# CH32F205RBT6-R1.net
KiCad netlist of a schematic drawn in Altium Designer
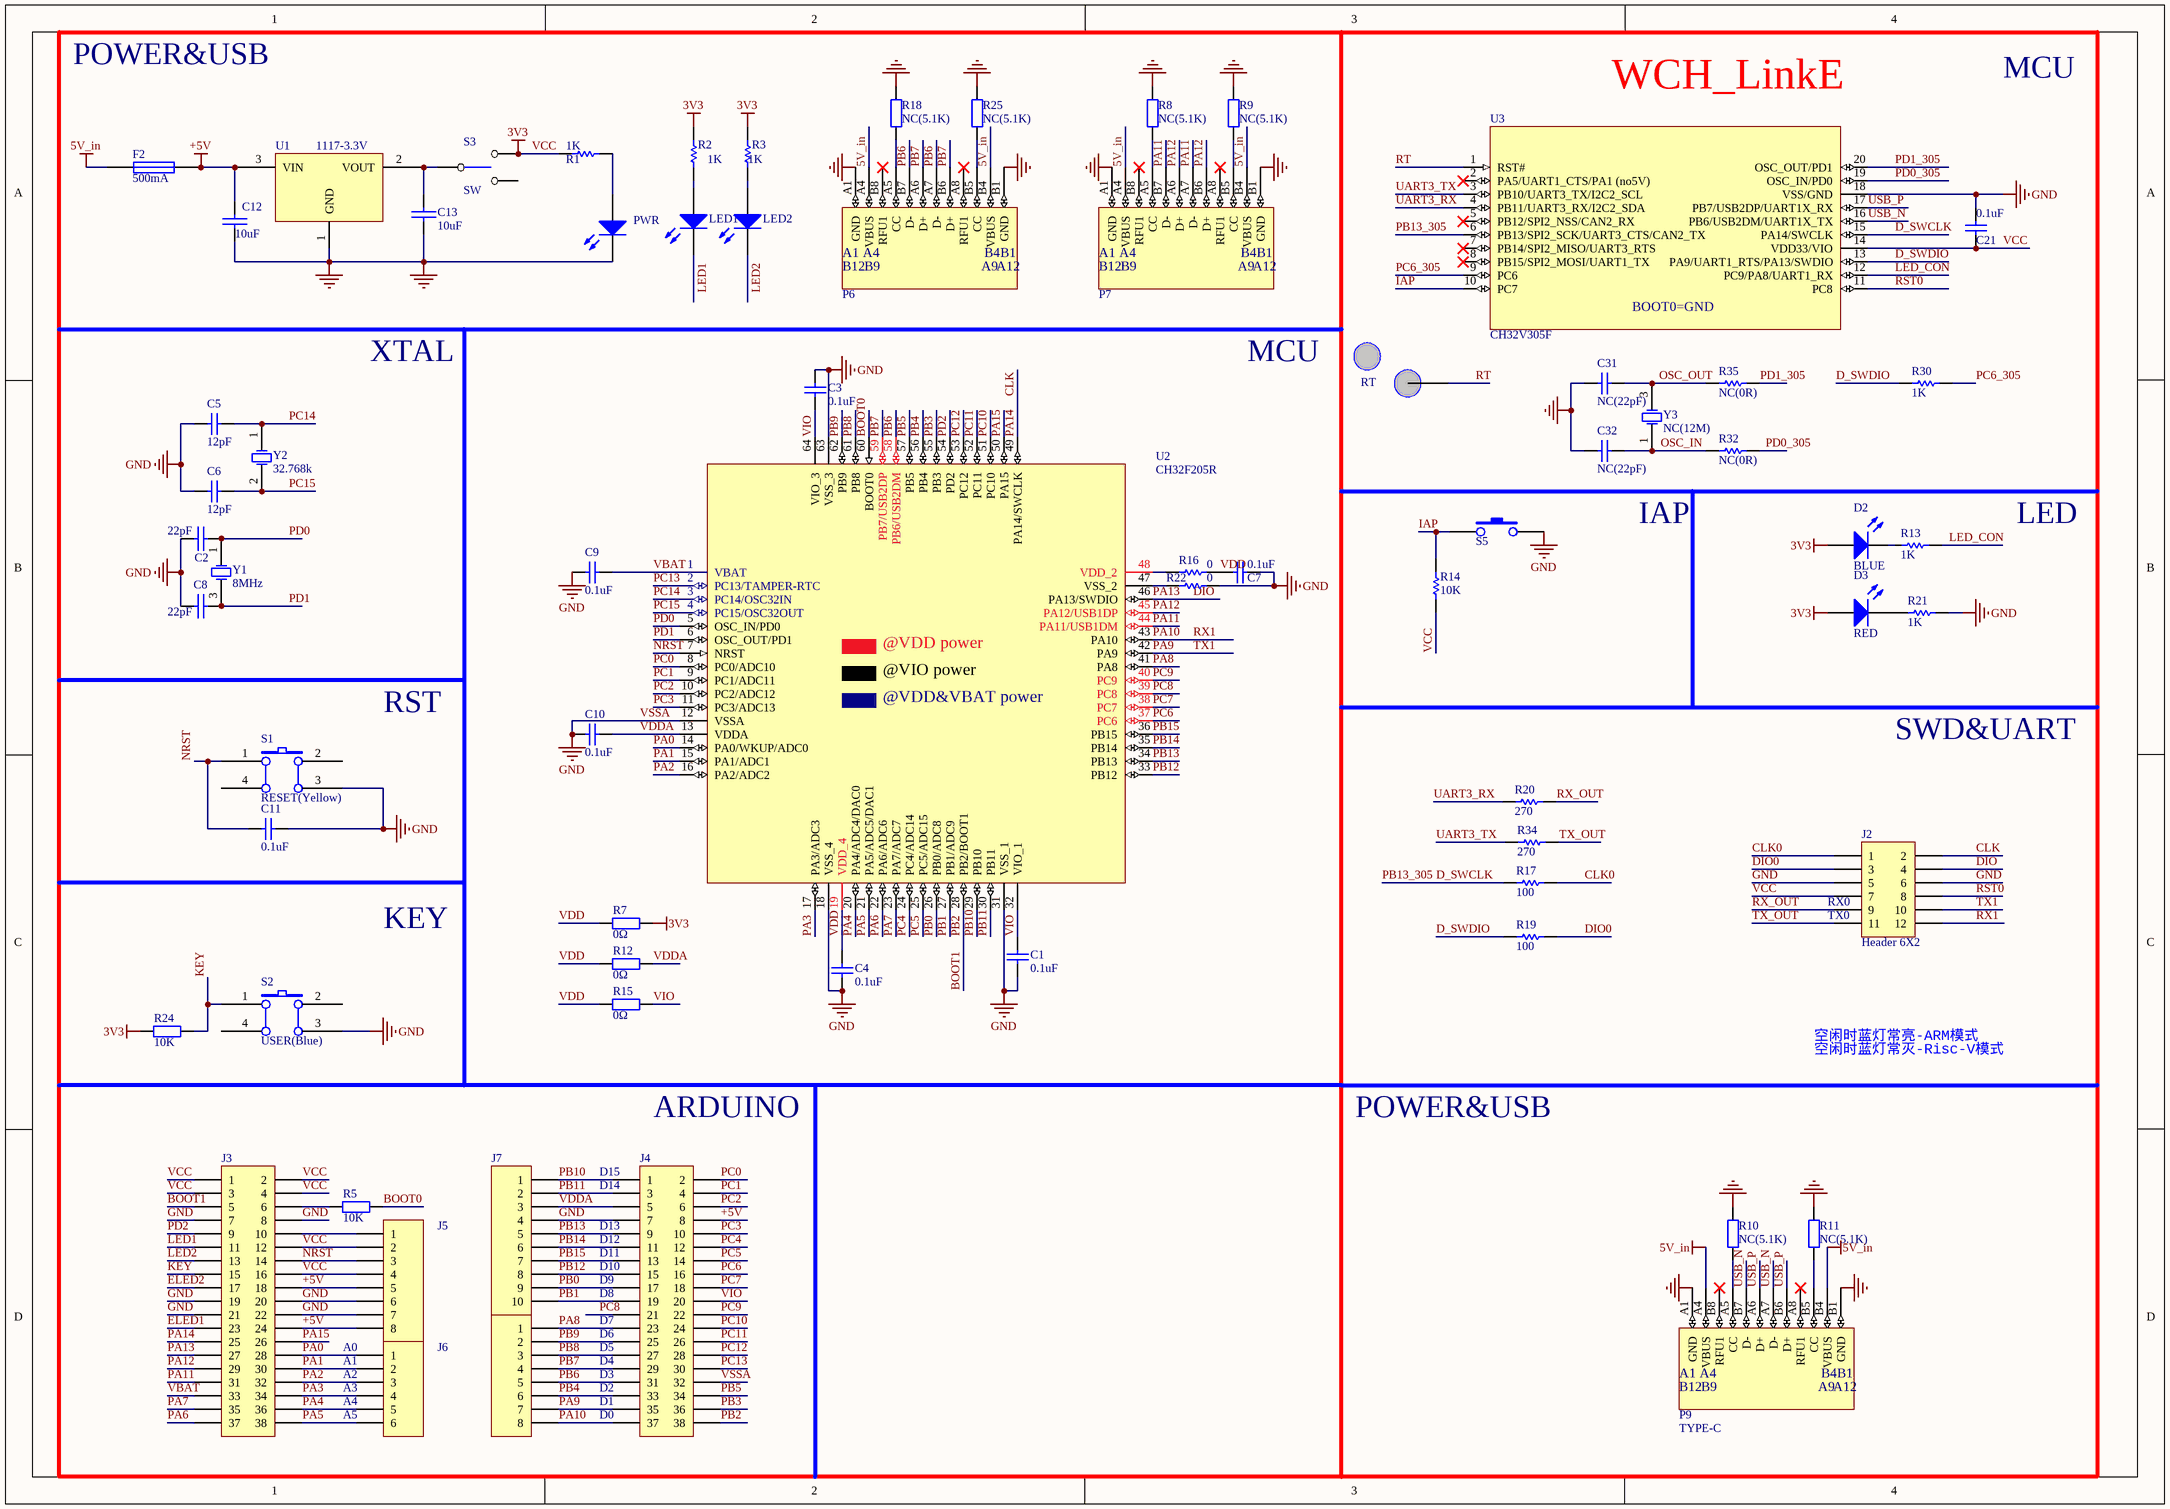
[diagram p0: CH32F205RBT6-R1.SchDoc]

(export (version "E")
  (design (tool "Eeschema 10.0.6"))
  (components
    (comp (ref "C1")
      (value "0.1uF")
      (footprint "0603_C")
      (description "Capacitor")
      (libsource (lib "Miscellaneous Devices") (part "Cap"))
    )
    (comp (ref "C2")
      (value "22pF")
      (footprint "0603_C")
      (description "Capacitor")
      (libsource (lib "*") (part "CAP"))
    )
    (comp (ref "C3")
      (value "0.1uF")
      (footprint "0603_C")
      (description "Capacitor")
      (libsource (lib "Miscellaneous Devices") (part "Cap"))
    )
    (comp (ref "C4")
      (value "0.1uF")
      (footprint "0603_C")
      (description "Capacitor")
      (libsource (lib "Miscellaneous Devices") (part "Cap"))
    )
    (comp (ref "C5")
      (value "12pF")
      (footprint "0603_C")
      (description "Capacitor")
      (libsource (lib "Miscellaneous Devices") (part "Cap"))
    )
    (comp (ref "C6")
      (value "12pF")
      (footprint "0603_C")
      (description "Capacitor")
      (libsource (lib "Miscellaneous Devices") (part "Cap"))
    )
    (comp (ref "C7")
      (value "0.1uF")
      (footprint "0603_C")
      (description "Capacitor")
      (libsource (lib "Miscellaneous Devices") (part "Cap"))
    )
    (comp (ref "C8")
      (value "22pF")
      (footprint "0603_C")
      (description "Capacitor")
      (libsource (lib "*") (part "CAP"))
    )
    (comp (ref "C9")
      (value "0.1uF")
      (footprint "0603_C")
      (description "Capacitor")
      (libsource (lib "Miscellaneous Devices") (part "Cap"))
    )
    (comp (ref "C10")
      (value "0.1uF")
      (footprint "0603_C")
      (description "Capacitor")
      (libsource (lib "Miscellaneous Devices") (part "Cap"))
    )
    (comp (ref "C11")
      (value "0.1uF")
      (footprint "0603_C")
      (description "Capacitor")
      (libsource (lib "Miscellaneous Devices") (part "Cap"))
    )
    (comp (ref "C12")
      (value "10uF")
      (footprint "3216_C")
      (description "Capacitor")
      (libsource (lib "*") (part "CAP"))
    )
    (comp (ref "C13")
      (value "10uF")
      (footprint "3216_C")
      (description "Capacitor")
      (libsource (lib "*") (part "CAP"))
    )
    (comp (ref "C21")
      (value "0.1uF")
      (footprint "0603_C")
      (description "Capacitor")
      (libsource (lib "Miscellaneous Devices") (part "Cap"))
    )
    (comp (ref "C31")
      (value "NC(22pF)")
      (footprint "0603_C")
      (description "Capacitor")
      (fields (field (name "PUBLISHER") "Altium Limited"))
      (libsource (lib "*") (part "Cap"))
    )
    (comp (ref "C32")
      (value "NC(22pF)")
      (footprint "0603_C")
      (description "Capacitor")
      (fields (field (name "PUBLISHER") "Altium Limited"))
      (libsource (lib "*") (part "Cap"))
    )
    (comp (ref "D2")
      (value "BLUE")
      (footprint "0603+")
      (description "Typical RED, GREEN, YELLOW, AMBER GaAs LED")
      (fields (field (name "PUBLISHER") "Altium Limited"))
      (libsource (lib "MYLIB") (part "D0603"))
    )
    (comp (ref "D3")
      (value "RED")
      (footprint "0603+")
      (description "Typical RED, GREEN, YELLOW, AMBER GaAs LED")
      (fields (field (name "PUBLISHER") "Altium Limited"))
      (libsource (lib "MYLIB") (part "D0603"))
    )
    (comp (ref "F2")
      (value "500mA")
      (footprint "0805")
      (description "Fuse")
      (libsource (lib "*") (part "FUSE1"))
    )
    (comp (ref "J2")
      (value "Header 6X2")
      (footprint "IDC12-2.54mm")
      (description "Header, 6-Pin, Dual row")
      (fields (field (name "PUBLISHER") "Altium Limited"))
      (libsource (lib "Miscellaneous Connectors") (part "Header 6X2"))
    )
    (comp (ref "J3")
      (value "Header 19X2")
      (footprint "IDC38-2.54mm")
      (description "Header, 19-Pin, Dual row")
      (fields (field (name "PUBLISHER") "Altium Limited"))
      (libsource (lib "Miscellaneous Connectors") (part "Header 19X2"))
    )
    (comp (ref "J4")
      (value "Header 19X2")
      (footprint "IDC38-2.54mm")
      (description "Header, 19-Pin, Dual row")
      (fields (field (name "PUBLISHER") "Altium Limited"))
      (libsource (lib "Miscellaneous Connectors") (part "Header 19X2"))
    )
    (comp (ref "J5")
      (value "Header 8")
      (footprint "SIP8-2.54mm")
      (description "Header, 8-Pin")
      (fields (field (name "PUBLISHER") "Altium Limited"))
      (libsource (lib "") (part "Header 8_1"))
    )
    (comp (ref "J6")
      (value "Header 6")
      (footprint "SIP6-2.54MM")
      (description "Header, 6-Pin")
      (fields (field (name "PUBLISHER") "Altium Limited"))
      (libsource (lib "Miscellaneous Connectors") (part "Header 6"))
    )
    (comp (ref "J7")
      (value "Header 10")
      (footprint "SIP10-2.54mm")
      (description "Header, 10-Pin")
      (fields (field (name "PUBLISHER") "Altium Limited"))
      (libsource (lib "Miscellaneous Connectors") (part "Header 10"))
    )
    (comp (ref "J8")
      (value "Header 8")
      (footprint "SIP8-2.54mm")
      (description "Header, 8-Pin")
      (fields (field (name "PUBLISHER") "Altium Limited"))
      (libsource (lib "Miscellaneous Connectors") (part "Header 8"))
    )
    (comp (ref "LED1")
      (value "LED1   blue")
      (footprint "0603+")
      (description "Typical INFRARED GaAs LED")
      (fields (field (name "PUBLISHER") "Altium Limited"))
      (libsource (lib "Miscellaneous Devices") (part "LED0"))
    )
    (comp (ref "LED2")
      (value "LED2  blue")
      (footprint "0603+")
      (description "Typical INFRARED GaAs LED")
      (fields (field (name "PUBLISHER") "Altium Limited"))
      (libsource (lib "Miscellaneous Devices") (part "LED0"))
    )
    (comp (ref "P6")
      (value "TYPE-C")
      (footprint "TYPE-C-Receptacle-2.0")
      (libsource (lib "*") (part "TYPE-C1"))
    )
    (comp (ref "P7")
      (value "TYPE-C")
      (footprint "TYPE-C-Receptacle-2.0")
      (libsource (lib "*") (part "TYPE-C1"))
    )
    (comp (ref "P9")
      (value "TYPE-C")
      (footprint "TYPE-C-Receptacle-2.0")
      (libsource (lib "*") (part "TYPE-C1"))
    )
    (comp (ref "PWR")
      (value "POWER  red")
      (footprint "0603+")
      (description "Typical INFRARED GaAs LED")
      (fields (field (name "PUBLISHER") "Altium Limited"))
      (libsource (lib "Miscellaneous Devices") (part "LED0"))
    )
    (comp (ref "R1")
      (value "1K")
      (footprint "0603")
      (description "Semiconductor Resistor")
      (libsource (lib "Miscellaneous Devices") (part "Res Semi"))
    )
    (comp (ref "R2")
      (value "1K")
      (footprint "0603")
      (description "Semiconductor Resistor")
      (libsource (lib "Miscellaneous Devices") (part "Res Semi"))
    )
    (comp (ref "R3")
      (value "1K")
      (footprint "0603")
      (description "Semiconductor Resistor")
      (libsource (lib "Miscellaneous Devices") (part "Res Semi"))
    )
    (comp (ref "R5")
      (value "10K")
      (footprint "0603")
      (description "Resistor")
      (libsource (lib "") (part "Res2_3"))
    )
    (comp (ref "R7")
      (value "0Ω")
      (footprint "0603")
      (description "Resistor")
      (libsource (lib "") (part "Res2_2"))
    )
    (comp (ref "R8")
      (value "NC(5.1K)")
      (footprint "0603")
      (description "Resistor")
      (libsource (lib "Miscellaneous Devices") (part "Res2"))
    )
    (comp (ref "R9")
      (value "NC(5.1K)")
      (footprint "0603")
      (description "Resistor")
      (libsource (lib "Miscellaneous Devices") (part "Res2"))
    )
    (comp (ref "R10")
      (value "NC(5.1K)")
      (footprint "0603")
      (description "Resistor")
      (libsource (lib "") (part "Res2_1"))
    )
    (comp (ref "R11")
      (value "NC(5.1K)")
      (footprint "0603")
      (description "Resistor")
      (libsource (lib "") (part "Res2_1"))
    )
    (comp (ref "R12")
      (value "0Ω")
      (footprint "0603")
      (description "Resistor")
      (libsource (lib "") (part "Res2_2"))
    )
    (comp (ref "R13")
      (value "1K")
      (footprint "0603")
      (description "Resistor")
      (fields (field (name "PUBLISHER") "Altium Limited"))
      (libsource (lib "MYLIB") (part "0603-1"))
    )
    (comp (ref "R14")
      (value "10K")
      (footprint "0603")
      (description "Resistor")
      (fields (field (name "PUBLISHER") "Altium Limited"))
      (libsource (lib "MYLIB") (part "0603-1"))
    )
    (comp (ref "R15")
      (value "0Ω")
      (footprint "0603")
      (description "Resistor")
      (libsource (lib "") (part "Res2_2"))
    )
    (comp (ref "R16")
      (value "0")
      (footprint "0603")
      (description "Resistor")
      (fields (field (name "PUBLISHER") "Altium Limited"))
      (libsource (lib "MYLIB") (part "0603-1"))
    )
    (comp (ref "R17")
      (value "100")
      (footprint "0603")
      (description "Resistor")
      (fields (field (name "PUBLISHER") "Altium Limited"))
      (libsource (lib "MYLIB") (part "0603-1"))
    )
    (comp (ref "R18")
      (value "NC(5.1K)")
      (footprint "0603")
      (description "Resistor")
      (libsource (lib "Miscellaneous Devices") (part "Res2"))
    )
    (comp (ref "R19")
      (value "100")
      (footprint "0603")
      (description "Resistor")
      (fields (field (name "PUBLISHER") "Altium Limited"))
      (libsource (lib "MYLIB") (part "0603-1"))
    )
    (comp (ref "R20")
      (value "270")
      (footprint "0603")
      (description "Resistor")
      (fields (field (name "PUBLISHER") "Altium Limited"))
      (libsource (lib "MYLIB") (part "0603-1"))
    )
    (comp (ref "R21")
      (value "1K")
      (footprint "0603")
      (description "Resistor")
      (fields (field (name "PUBLISHER") "Altium Limited"))
      (libsource (lib "MYLIB") (part "0603-1"))
    )
    (comp (ref "R22")
      (value "0")
      (footprint "0603")
      (description "Resistor")
      (fields (field (name "PUBLISHER") "Altium Limited"))
      (libsource (lib "MYLIB") (part "0603-1"))
    )
    (comp (ref "R24")
      (value "10K")
      (footprint "0603")
      (description "Resistor")
      (libsource (lib "") (part "Res2_2"))
    )
    (comp (ref "R25")
      (value "NC(5.1K)")
      (footprint "0603")
      (description "Resistor")
      (libsource (lib "Miscellaneous Devices") (part "Res2"))
    )
    (comp (ref "R30")
      (value "1K")
      (footprint "0603")
      (description "Resistor")
      (fields (field (name "PUBLISHER") "Altium Limited"))
      (libsource (lib "MYLIB") (part "0603-1"))
    )
    (comp (ref "R32")
      (value "NC(0R)")
      (footprint "0603")
      (description "Resistor")
      (fields (field (name "PUBLISHER") "Altium Limited"))
      (libsource (lib "MYLIB") (part "0603-1"))
    )
    (comp (ref "R34")
      (value "270")
      (footprint "0603")
      (description "Resistor")
      (fields (field (name "PUBLISHER") "Altium Limited"))
      (libsource (lib "MYLIB") (part "0603-1"))
    )
    (comp (ref "R35")
      (value "NC(0R)")
      (footprint "0603")
      (description "Resistor")
      (fields (field (name "PUBLISHER") "Altium Limited"))
      (libsource (lib "MYLIB") (part "0603-1"))
    )
    (comp (ref "RT")
      (value "Testpoint")
      (footprint "TESTPOINT1")
      (description "测试点")
      (libsource (lib "wch_sch_others") (part "Testpoint"))
    )
    (comp (ref "S1")
      (value "RESET(Yellow)")
      (footprint "KEYX")
      (description "SE PUSHBUTTON")
      (libsource (lib "Documents") (part "SW PUSHBUTTON"))
    )
    (comp (ref "S2")
      (value "USER(Blue)")
      (footprint "KEYX")
      (description "SE PUSHBUTTON")
      (libsource (lib "Documents") (part "SW PUSHBUTTON"))
    )
    (comp (ref "S3") (value "SW") (footprint "SW1") (libsource (lib "MYSCH") (part "SW")))
    (comp (ref "S5") (value "KEY") (footprint "贴片按键") (libsource (lib "*") (part "KEY")))
    (comp (ref "U1")
      (value "1117-3.3V")
      (footprint "SOT-223")
      (libsource (lib "wch_sch_others") (part "1117-3.3V"))
    )
    (comp (ref "U2")
      (value "CH32F205R")
      (footprint "LQFP64M_10x10")
      (description "ARM M3 HD-MCU, 144MHz, USB_480M, USB OTG, 2*CAN, 4*OPA")
      (libsource (lib "CHXXX") (part "CH32F205R"))
    )
    (comp (ref "U3")
      (value "CH32V305F")
      (footprint "TSSOP20")
      (description "RISC-V FPU HD-MCU, 144MHz, USB_480M, CAN, UART*2, SPI")
      (libsource (lib "CHXXX") (part "CH32V305F"))
    )
    (comp (ref "Y1")
      (value "8MHz")
      (footprint "XT3225")
      (description "Crystal Oscillator")
      (fields (field (name "PUBLISHER") "Altium Limited"))
      (libsource (lib "*") (part "XTAL"))
    )
    (comp (ref "Y2")
      (value "32.768k")
      (footprint "FC-135")
      (description "Crystal Oscillator")
      (fields (field (name "PUBLISHER") "Altium Limited"))
      (libsource (lib "Miscellaneous Devices") (part "XTAL"))
    )
    (comp (ref "Y3")
      (value "NC(12M)")
      (footprint "XT3225")
      (description "Crystal Oscillator")
      (libsource (lib "*") (part "XTAL"))
    )
  )
  (nets
    (net (code "1") (name "+5V") (class "Default")
      (node (ref "C12") (pin "1") (pinfunction "1_1") (pintype "passive"))
      (node (ref "F2") (pin "2") (pinfunction "2_2") (pintype "passive"))
      (node (ref "J3") (pin "18") (pinfunction "18_18") (pintype "passive"))
      (node (ref "J3") (pin "24") (pinfunction "24_24") (pintype "passive"))
      (node (ref "J4") (pin "8") (pinfunction "8_8") (pintype "passive"))
      (node (ref "J5") (pin "5") (pinfunction "5_5") (pintype "passive"))
      (node (ref "J5") (pin "8") (pinfunction "8_8") (pintype "passive"))
      (node (ref "U1") (pin "3") (pinfunction "VIN_3") (pintype "passive"))
    )
    (net (code "2") (name "/BOOT0") (class "Default")
      (node (ref "R5") (pin "2") (pinfunction "2_2") (pintype "passive"))
      (node (ref "U2") (pin "60") (pinfunction "BOOT0_60") (pintype "input"))
    )
    (net (code "3") (name "/BOOT1") (class "Default")
      (node (ref "J3") (pin "5") (pinfunction "5_5") (pintype "passive"))
      (node (ref "J4") (pin "38") (pinfunction "38_38") (pintype "passive"))
      (node (ref "U2") (pin "28") (pinfunction "PB2/BOOT1_28") (pintype "bidirectional"))
    )
    (net (code "4") (name "/CLK") (class "Default")
      (node (ref "J2") (pin "2") (pinfunction "2_2") (pintype "passive"))
      (node (ref "J3") (pin "25") (pinfunction "25_25") (pintype "passive"))
      (node (ref "U2") (pin "49") (pinfunction "PA14/SWCLK_49") (pintype "bidirectional"))
    )
    (net (code "5") (name "/CLK0") (class "Default")
      (node (ref "J2") (pin "1") (pinfunction "1_1") (pintype "passive"))
      (node (ref "R17") (pin "1") (pinfunction "1_1") (pintype "passive"))
    )
    (net (code "6") (name "/DIO") (class "Default")
      (node (ref "J2") (pin "4") (pinfunction "4_4") (pintype "passive"))
      (node (ref "J3") (pin "27") (pinfunction "27_27") (pintype "passive"))
      (node (ref "U2") (pin "46") (pinfunction "PA13/SWDIO_46") (pintype "bidirectional"))
    )
    (net (code "7") (name "/DIO0") (class "Default")
      (node (ref "J2") (pin "3") (pinfunction "3_3") (pintype "passive"))
      (node (ref "R19") (pin "1") (pinfunction "1_1") (pintype "passive"))
    )
    (net (code "8") (name "/D_SWCLK") (class "Default")
      (node (ref "R17") (pin "2") (pinfunction "2_2") (pintype "passive"))
      (node (ref "U3") (pin "15") (pinfunction "PA14/SWCLK_15") (pintype "bidirectional"))
      (node (ref "U3") (pin "6") (pinfunction "PB13/SPI2_SCK/UART3_CTS/CAN2_TX_6") (pintype "bidirectional"))
    )
    (net (code "9") (name "/D_SWDIO") (class "Default")
      (node (ref "R19") (pin "2") (pinfunction "2_2") (pintype "passive"))
      (node (ref "R30") (pin "1") (pinfunction "1_1") (pintype "passive"))
      (node (ref "U3") (pin "13") (pinfunction "PA9/UART1_RTS/PA13/SWDIO_13") (pintype "bidirectional"))
    )
    (net (code "10") (name "/ELED1") (class "Default")
      (node (ref "J3") (pin "23") (pinfunction "23_23") (pintype "passive"))
    )
    (net (code "11") (name "/ELED2") (class "Default")
      (node (ref "J3") (pin "17") (pinfunction "17_17") (pintype "passive"))
    )
    (net (code "12") (name "/IAP") (class "Default")
      (node (ref "R14") (pin "1") (pinfunction "1_1") (pintype "passive"))
      (node (ref "S5") (pin "1") (pinfunction "1_1") (pintype "passive"))
      (node (ref "U3") (pin "10") (pinfunction "PC7_10") (pintype "bidirectional"))
    )
    (net (code "13") (name "/KEY") (class "Default")
      (node (ref "J3") (pin "15") (pinfunction "15_15") (pintype "passive"))
      (node (ref "R24") (pin "1") (pinfunction "1_1") (pintype "passive"))
      (node (ref "S2") (pin "1") (pinfunction "A0_1") (pintype "passive"))
    )
    (net (code "14") (name "/LED1") (class "Default")
      (node (ref "J3") (pin "11") (pinfunction "11_11") (pintype "passive"))
      (node (ref "LED1") (pin "2") (pinfunction "K_2") (pintype "passive"))
    )
    (net (code "15") (name "/LED2") (class "Default")
      (node (ref "J3") (pin "13") (pinfunction "13_13") (pintype "passive"))
      (node (ref "LED2") (pin "2") (pinfunction "K_2") (pintype "passive"))
    )
    (net (code "16") (name "/LED_CON") (class "Default")
      (node (ref "R13") (pin "1") (pinfunction "1_1") (pintype "passive"))
      (node (ref "U3") (pin "12") (pinfunction "PC9/PA8/UART1_RX_12") (pintype "bidirectional"))
    )
    (net (code "17") (name "/NRST") (class "Default")
      (node (ref "C11") (pin "2") (pinfunction "2_2") (pintype "passive"))
      (node (ref "J3") (pin "14") (pinfunction "14_14") (pintype "passive"))
      (node (ref "J5") (pin "3") (pinfunction "3_3") (pintype "passive"))
      (node (ref "S1") (pin "1") (pinfunction "A0_1") (pintype "passive"))
      (node (ref "U2") (pin "7") (pinfunction "NRST_7") (pintype "input"))
    )
    (net (code "18") (name "/OSC_IN") (class "Default")
      (node (ref "C32") (pin "2") (pinfunction "2_2") (pintype "passive"))
      (node (ref "R32") (pin "2") (pinfunction "2_2") (pintype "passive"))
      (node (ref "Y3") (pin "1") (pinfunction "OSC1_1") (pintype "passive"))
    )
    (net (code "19") (name "/OSC_OUT") (class "Default")
      (node (ref "C31") (pin "2") (pinfunction "2_2") (pintype "passive"))
      (node (ref "R35") (pin "2") (pinfunction "2_2") (pintype "passive"))
      (node (ref "Y3") (pin "3") (pinfunction "OSC2_3") (pintype "passive"))
    )
    (net (code "20") (name "/PA0") (class "Default")
      (node (ref "J3") (pin "28") (pinfunction "28_28") (pintype "passive"))
      (node (ref "J6") (pin "1") (pinfunction "1_1") (pintype "passive"))
      (node (ref "U2") (pin "14") (pinfunction "PA0/WKUP/ADC0_14") (pintype "bidirectional"))
    )
    (net (code "21") (name "/PA1") (class "Default")
      (node (ref "J3") (pin "30") (pinfunction "30_30") (pintype "passive"))
      (node (ref "J6") (pin "2") (pinfunction "2_2") (pintype "passive"))
      (node (ref "U2") (pin "15") (pinfunction "PA1/ADC1_15") (pintype "bidirectional"))
    )
    (net (code "22") (name "/PA2") (class "Default")
      (node (ref "J3") (pin "32") (pinfunction "32_32") (pintype "passive"))
      (node (ref "J6") (pin "3") (pinfunction "3_3") (pintype "passive"))
      (node (ref "U2") (pin "16") (pinfunction "PA2/ADC2_16") (pintype "bidirectional"))
    )
    (net (code "23") (name "/PA3") (class "Default")
      (node (ref "J3") (pin "34") (pinfunction "34_34") (pintype "passive"))
      (node (ref "J6") (pin "4") (pinfunction "4_4") (pintype "passive"))
      (node (ref "U2") (pin "17") (pinfunction "PA3/ADC3_17") (pintype "bidirectional"))
    )
    (net (code "24") (name "/PA4") (class "Default")
      (node (ref "J3") (pin "36") (pinfunction "36_36") (pintype "passive"))
      (node (ref "J6") (pin "5") (pinfunction "5_5") (pintype "passive"))
      (node (ref "U2") (pin "20") (pinfunction "PA4/ADC4/DAC0_20") (pintype "bidirectional"))
    )
    (net (code "25") (name "/PA5") (class "Default")
      (node (ref "J3") (pin "38") (pinfunction "38_38") (pintype "passive"))
      (node (ref "J6") (pin "6") (pinfunction "6_6") (pintype "passive"))
      (node (ref "U2") (pin "21") (pinfunction "PA5/ADC5/DAC1_21") (pintype "bidirectional"))
    )
    (net (code "26") (name "/PA6") (class "Default")
      (node (ref "J3") (pin "37") (pinfunction "37_37") (pintype "passive"))
      (node (ref "U2") (pin "22") (pinfunction "PA6/ADC6_22") (pintype "bidirectional"))
    )
    (net (code "27") (name "/PA7") (class "Default")
      (node (ref "J3") (pin "35") (pinfunction "35_35") (pintype "passive"))
      (node (ref "U2") (pin "23") (pinfunction "PA7/ADC7_23") (pintype "bidirectional"))
    )
    (net (code "28") (name "/PA8") (class "Default")
      (node (ref "J4") (pin "23") (pinfunction "23_23") (pintype "passive"))
      (node (ref "J8") (pin "1") (pinfunction "1_1") (pintype "passive"))
      (node (ref "U2") (pin "41") (pinfunction "PA8_41") (pintype "bidirectional"))
    )
    (net (code "29") (name "/PA9") (class "Default")
      (node (ref "J2") (pin "10") (pinfunction "10_10") (pintype "passive"))
      (node (ref "J4") (pin "35") (pinfunction "35_35") (pintype "passive"))
      (node (ref "J8") (pin "7") (pinfunction "7_7") (pintype "passive"))
      (node (ref "U2") (pin "42") (pinfunction "PA9_42") (pintype "bidirectional"))
    )
    (net (code "30") (name "/PA10") (class "Default")
      (node (ref "J2") (pin "12") (pinfunction "12_12") (pintype "passive"))
      (node (ref "J4") (pin "37") (pinfunction "37_37") (pintype "passive"))
      (node (ref "J8") (pin "8") (pinfunction "8_8") (pintype "passive"))
      (node (ref "U2") (pin "43") (pinfunction "PA10_43") (pintype "bidirectional"))
    )
    (net (code "31") (name "/PA11") (class "Default")
      (node (ref "J3") (pin "31") (pinfunction "31_31") (pintype "passive"))
      (node (ref "P7") (pin "A7") (pinfunction "D-_A7") (pintype "bidirectional"))
      (node (ref "P7") (pin "B7") (pinfunction "D-_B7") (pintype "bidirectional"))
      (node (ref "U2") (pin "44") (pinfunction "PA11/USB1DM_44") (pintype "bidirectional"))
    )
    (net (code "32") (name "/PA12") (class "Default")
      (node (ref "J3") (pin "29") (pinfunction "29_29") (pintype "passive"))
      (node (ref "P7") (pin "A6") (pinfunction "D+_A6") (pintype "bidirectional"))
      (node (ref "P7") (pin "B6") (pinfunction "D+_B6") (pintype "bidirectional"))
      (node (ref "U2") (pin "45") (pinfunction "PA12/USB1DP_45") (pintype "bidirectional"))
    )
    (net (code "33") (name "/PA15") (class "Default")
      (node (ref "J3") (pin "26") (pinfunction "26_26") (pintype "passive"))
      (node (ref "U2") (pin "50") (pinfunction "PA15_50") (pintype "bidirectional"))
    )
    (net (code "34") (name "/PB0") (class "Default")
      (node (ref "J4") (pin "17") (pinfunction "17_17") (pintype "passive"))
      (node (ref "J7") (pin "9") (pinfunction "9_9") (pintype "passive"))
      (node (ref "U2") (pin "26") (pinfunction "PB0/ADC8_26") (pintype "bidirectional"))
    )
    (net (code "35") (name "/PB1") (class "Default")
      (node (ref "J4") (pin "19") (pinfunction "19_19") (pintype "passive"))
      (node (ref "J7") (pin "10") (pinfunction "10_10") (pintype "passive"))
      (node (ref "U2") (pin "27") (pinfunction "PB1/ADC9_27") (pintype "bidirectional"))
    )
    (net (code "36") (name "/PB3") (class "Default")
      (node (ref "J4") (pin "36") (pinfunction "36_36") (pintype "passive"))
      (node (ref "U2") (pin "55") (pinfunction "PB3_55") (pintype "bidirectional"))
    )
    (net (code "37") (name "/PB4") (class "Default")
      (node (ref "J4") (pin "33") (pinfunction "33_33") (pintype "passive"))
      (node (ref "J8") (pin "6") (pinfunction "6_6") (pintype "passive"))
      (node (ref "U2") (pin "56") (pinfunction "PB4_56") (pintype "bidirectional"))
    )
    (net (code "38") (name "/PB5") (class "Default")
      (node (ref "J4") (pin "34") (pinfunction "34_34") (pintype "passive"))
      (node (ref "U2") (pin "57") (pinfunction "PB5_57") (pintype "bidirectional"))
    )
    (net (code "39") (name "/PB6") (class "Default")
      (node (ref "J4") (pin "31") (pinfunction "31_31") (pintype "passive"))
      (node (ref "J8") (pin "5") (pinfunction "5_5") (pintype "passive"))
      (node (ref "P6") (pin "A7") (pinfunction "D-_A7") (pintype "bidirectional"))
      (node (ref "P6") (pin "B7") (pinfunction "D-_B7") (pintype "bidirectional"))
      (node (ref "U2") (pin "58") (pinfunction "PB6/USB2DM_58") (pintype "bidirectional"))
    )
    (net (code "40") (name "/PB7") (class "Default")
      (node (ref "J4") (pin "29") (pinfunction "29_29") (pintype "passive"))
      (node (ref "J8") (pin "4") (pinfunction "4_4") (pintype "passive"))
      (node (ref "P6") (pin "A6") (pinfunction "D+_A6") (pintype "bidirectional"))
      (node (ref "P6") (pin "B6") (pinfunction "D+_B6") (pintype "bidirectional"))
      (node (ref "U2") (pin "59") (pinfunction "PB7/USB2DP_59") (pintype "bidirectional"))
    )
    (net (code "41") (name "/PB8") (class "Default")
      (node (ref "J4") (pin "27") (pinfunction "27_27") (pintype "passive"))
      (node (ref "J8") (pin "3") (pinfunction "3_3") (pintype "passive"))
      (node (ref "U2") (pin "61") (pinfunction "PB8_61") (pintype "bidirectional"))
    )
    (net (code "42") (name "/PB9") (class "Default")
      (node (ref "J4") (pin "25") (pinfunction "25_25") (pintype "passive"))
      (node (ref "J8") (pin "2") (pinfunction "2_2") (pintype "passive"))
      (node (ref "U2") (pin "62") (pinfunction "PB9_62") (pintype "bidirectional"))
    )
    (net (code "43") (name "/PB10") (class "Default")
      (node (ref "J4") (pin "1") (pinfunction "1_1") (pintype "passive"))
      (node (ref "J7") (pin "1") (pinfunction "1_1") (pintype "passive"))
      (node (ref "U2") (pin "29") (pinfunction "PB10_29") (pintype "bidirectional"))
    )
    (net (code "44") (name "/PB11") (class "Default")
      (node (ref "J4") (pin "3") (pinfunction "3_3") (pintype "passive"))
      (node (ref "J7") (pin "2") (pinfunction "2_2") (pintype "passive"))
      (node (ref "U2") (pin "30") (pinfunction "PB11_30") (pintype "bidirectional"))
    )
    (net (code "45") (name "/PB12") (class "Default")
      (node (ref "J4") (pin "15") (pinfunction "15_15") (pintype "passive"))
      (node (ref "J7") (pin "8") (pinfunction "8_8") (pintype "passive"))
      (node (ref "U2") (pin "33") (pinfunction "PB12_33") (pintype "bidirectional"))
    )
    (net (code "46") (name "/PB13") (class "Default")
      (node (ref "J4") (pin "9") (pinfunction "9_9") (pintype "passive"))
      (node (ref "J7") (pin "5") (pinfunction "5_5") (pintype "passive"))
      (node (ref "U2") (pin "34") (pinfunction "PB13_34") (pintype "bidirectional"))
    )
    (net (code "47") (name "/PB14") (class "Default")
      (node (ref "J4") (pin "11") (pinfunction "11_11") (pintype "passive"))
      (node (ref "J7") (pin "6") (pinfunction "6_6") (pintype "passive"))
      (node (ref "U2") (pin "35") (pinfunction "PB14_35") (pintype "bidirectional"))
    )
    (net (code "48") (name "/PB15") (class "Default")
      (node (ref "J4") (pin "13") (pinfunction "13_13") (pintype "passive"))
      (node (ref "J7") (pin "7") (pinfunction "7_7") (pintype "passive"))
      (node (ref "U2") (pin "36") (pinfunction "PB15_36") (pintype "bidirectional"))
    )
    (net (code "49") (name "/PC0") (class "Default")
      (node (ref "J4") (pin "2") (pinfunction "2_2") (pintype "passive"))
      (node (ref "U2") (pin "8") (pinfunction "PC0/ADC10_8") (pintype "bidirectional"))
    )
    (net (code "50") (name "/PC1") (class "Default")
      (node (ref "J4") (pin "4") (pinfunction "4_4") (pintype "passive"))
      (node (ref "U2") (pin "9") (pinfunction "PC1/ADC11_9") (pintype "bidirectional"))
    )
    (net (code "51") (name "/PC2") (class "Default")
      (node (ref "J4") (pin "6") (pinfunction "6_6") (pintype "passive"))
      (node (ref "U2") (pin "10") (pinfunction "PC2/ADC12_10") (pintype "bidirectional"))
    )
    (net (code "52") (name "/PC3") (class "Default")
      (node (ref "J4") (pin "10") (pinfunction "10_10") (pintype "passive"))
      (node (ref "U2") (pin "11") (pinfunction "PC3/ADC13_11") (pintype "bidirectional"))
    )
    (net (code "53") (name "/PC4") (class "Default")
      (node (ref "J4") (pin "12") (pinfunction "12_12") (pintype "passive"))
      (node (ref "U2") (pin "24") (pinfunction "PC4/ADC14_24") (pintype "bidirectional"))
    )
    (net (code "54") (name "/PC5") (class "Default")
      (node (ref "J4") (pin "14") (pinfunction "14_14") (pintype "passive"))
      (node (ref "U2") (pin "25") (pinfunction "PC5/ADC15_25") (pintype "bidirectional"))
    )
    (net (code "55") (name "/PC6") (class "Default")
      (node (ref "J4") (pin "16") (pinfunction "16_16") (pintype "passive"))
      (node (ref "U2") (pin "37") (pinfunction "PC6_37") (pintype "bidirectional"))
    )
    (net (code "56") (name "/PC6_305") (class "Default")
      (node (ref "R30") (pin "2") (pinfunction "2_2") (pintype "passive"))
      (node (ref "U3") (pin "9") (pinfunction "PC6_9") (pintype "bidirectional"))
    )
    (net (code "57") (name "/PC7") (class "Default")
      (node (ref "J4") (pin "18") (pinfunction "18_18") (pintype "passive"))
      (node (ref "U2") (pin "38") (pinfunction "PC7_38") (pintype "bidirectional"))
    )
    (net (code "58") (name "/PC8") (class "Default")
      (node (ref "J4") (pin "21") (pinfunction "21_21") (pintype "passive"))
      (node (ref "U2") (pin "39") (pinfunction "PC8_39") (pintype "bidirectional"))
    )
    (net (code "59") (name "/PC9") (class "Default")
      (node (ref "J4") (pin "22") (pinfunction "22_22") (pintype "passive"))
      (node (ref "U2") (pin "40") (pinfunction "PC9_40") (pintype "bidirectional"))
    )
    (net (code "60") (name "/PC10") (class "Default")
      (node (ref "J4") (pin "24") (pinfunction "24_24") (pintype "passive"))
      (node (ref "U2") (pin "51") (pinfunction "PC10_51") (pintype "bidirectional"))
    )
    (net (code "61") (name "/PC11") (class "Default")
      (node (ref "J4") (pin "26") (pinfunction "26_26") (pintype "passive"))
      (node (ref "U2") (pin "52") (pinfunction "PC11_52") (pintype "bidirectional"))
    )
    (net (code "62") (name "/PC12") (class "Default")
      (node (ref "J4") (pin "28") (pinfunction "28_28") (pintype "passive"))
      (node (ref "U2") (pin "53") (pinfunction "PC12_53") (pintype "bidirectional"))
    )
    (net (code "63") (name "/PC13") (class "Default")
      (node (ref "J4") (pin "30") (pinfunction "30_30") (pintype "passive"))
      (node (ref "U2") (pin "2") (pinfunction "PC13/TAMPER-RTC_2") (pintype "bidirectional"))
    )
    (net (code "64") (name "/PC14") (class "Default")
      (node (ref "C5") (pin "1") (pinfunction "1_1") (pintype "passive"))
      (node (ref "U2") (pin "3") (pinfunction "PC14/OSC32IN_3") (pintype "bidirectional"))
      (node (ref "Y2") (pin "1") (pinfunction "OSC1_1") (pintype "passive"))
    )
    (net (code "65") (name "/PC15") (class "Default")
      (node (ref "C6") (pin "1") (pinfunction "1_1") (pintype "passive"))
      (node (ref "U2") (pin "4") (pinfunction "PC15/OSC32OUT_4") (pintype "bidirectional"))
      (node (ref "Y2") (pin "2") (pinfunction "OSC2_2") (pintype "passive"))
    )
    (net (code "66") (name "/PD0") (class "Default")
      (node (ref "C2") (pin "2") (pinfunction "2_2") (pintype "passive"))
      (node (ref "U2") (pin "5") (pinfunction "OSC_IN/PD0_5") (pintype "bidirectional"))
      (node (ref "Y1") (pin "1") (pinfunction "OSC1_1") (pintype "passive"))
    )
    (net (code "67") (name "/PD0_305") (class "Default")
      (node (ref "R32") (pin "1") (pinfunction "1_1") (pintype "passive"))
      (node (ref "U3") (pin "19") (pinfunction "OSC_IN/PD0_19") (pintype "bidirectional"))
    )
    (net (code "68") (name "/PD1") (class "Default")
      (node (ref "C8") (pin "2") (pinfunction "2_2") (pintype "passive"))
      (node (ref "U2") (pin "6") (pinfunction "OSC_OUT/PD1_6") (pintype "bidirectional"))
      (node (ref "Y1") (pin "3") (pinfunction "OSC2_3") (pintype "passive"))
    )
    (net (code "69") (name "/PD1_305") (class "Default")
      (node (ref "R35") (pin "1") (pinfunction "1_1") (pintype "passive"))
      (node (ref "U3") (pin "20") (pinfunction "OSC_OUT/PD1_20") (pintype "bidirectional"))
    )
    (net (code "70") (name "/PD2") (class "Default")
      (node (ref "J3") (pin "9") (pinfunction "9_9") (pintype "passive"))
      (node (ref "U2") (pin "54") (pinfunction "PD2_54") (pintype "bidirectional"))
    )
    (net (code "71") (name "/RST0") (class "Default")
      (node (ref "J2") (pin "8") (pinfunction "8_8") (pintype "passive"))
      (node (ref "U3") (pin "11") (pinfunction "PC8_11") (pintype "bidirectional"))
    )
    (net (code "72") (name "/RT") (class "Default")
      (node (ref "RT") (pin "1") (pinfunction "point_1") (pintype "passive"))
      (node (ref "U3") (pin "1") (pinfunction "RST#_1") (pintype "input"))
    )
    (net (code "73") (name "/RX_OUT") (class "Default")
      (node (ref "J2") (pin "9") (pinfunction "9_9") (pintype "passive"))
      (node (ref "R20") (pin "1") (pinfunction "1_1") (pintype "passive"))
    )
    (net (code "74") (name "/TX_OUT") (class "Default")
      (node (ref "J2") (pin "11") (pinfunction "11_11") (pintype "passive"))
      (node (ref "R34") (pin "1") (pinfunction "1_1") (pintype "passive"))
    )
    (net (code "75") (name "/UART3_RX") (class "Default")
      (node (ref "R20") (pin "2") (pinfunction "2_2") (pintype "passive"))
      (node (ref "U3") (pin "4") (pinfunction "PB11/UART3_RX/I2C2_SDA_4") (pintype "bidirectional"))
    )
    (net (code "76") (name "/UART3_TX") (class "Default")
      (node (ref "R34") (pin "2") (pinfunction "2_2") (pintype "passive"))
      (node (ref "U3") (pin "3") (pinfunction "PB10/UART3_TX/I2C2_SCL_3") (pintype "bidirectional"))
    )
    (net (code "77") (name "/USB_N") (class "Default")
      (node (ref "P9") (pin "A7") (pinfunction "D-_A7") (pintype "bidirectional"))
      (node (ref "P9") (pin "B7") (pinfunction "D-_B7") (pintype "bidirectional"))
      (node (ref "U3") (pin "16") (pinfunction "PB6/USB2DM/UART1X_TX_16") (pintype "bidirectional"))
    )
    (net (code "78") (name "/USB_P") (class "Default")
      (node (ref "P9") (pin "A6") (pinfunction "D+_A6") (pintype "bidirectional"))
      (node (ref "P9") (pin "B6") (pinfunction "D+_B6") (pintype "bidirectional"))
      (node (ref "U3") (pin "17") (pinfunction "PB7/USB2DP/UART1X_RX_17") (pintype "bidirectional"))
    )
    (net (code "79") (name "/VBAT") (class "Default")
      (node (ref "C9") (pin "1") (pinfunction "1_1") (pintype "passive"))
      (node (ref "J3") (pin "33") (pinfunction "33_33") (pintype "passive"))
      (node (ref "U2") (pin "1") (pinfunction "VBAT_1") (pintype "power_in"))
    )
    (net (code "80") (name "/VDD") (class "Default")
      (node (ref "C4") (pin "2") (pinfunction "2_2") (pintype "passive"))
      (node (ref "C7") (pin "2") (pinfunction "2_2") (pintype "passive"))
      (node (ref "R12") (pin "2") (pinfunction "2_2") (pintype "passive"))
      (node (ref "R15") (pin "2") (pinfunction "2_2") (pintype "passive"))
      (node (ref "R16") (pin "1") (pinfunction "1_1") (pintype "passive"))
      (node (ref "R7") (pin "2") (pinfunction "2_2") (pintype "passive"))
      (node (ref "U2") (pin "19") (pinfunction "VDD_4_19") (pintype "power_in"))
    )
    (net (code "81") (name "/VDDA") (class "Default")
      (node (ref "C10") (pin "1") (pinfunction "1_1") (pintype "passive"))
      (node (ref "J4") (pin "5") (pinfunction "5_5") (pintype "passive"))
      (node (ref "J7") (pin "3") (pinfunction "3_3") (pintype "passive"))
      (node (ref "R12") (pin "1") (pinfunction "1_1") (pintype "passive"))
      (node (ref "U2") (pin "13") (pinfunction "VDDA_13") (pintype "power_in"))
    )
    (net (code "82") (name "/VIO") (class "Default")
      (node (ref "C1") (pin "2") (pinfunction "2_2") (pintype "passive"))
      (node (ref "C3") (pin "2") (pinfunction "2_2") (pintype "passive"))
      (node (ref "J4") (pin "20") (pinfunction "20_20") (pintype "passive"))
      (node (ref "R15") (pin "1") (pinfunction "1_1") (pintype "passive"))
      (node (ref "U2") (pin "32") (pinfunction "VIO_1_32") (pintype "power_in"))
      (node (ref "U2") (pin "64") (pinfunction "VIO_3_64") (pintype "power_in"))
    )
    (net (code "83") (name "3V3") (class "Default")
      (node (ref "C21") (pin "1") (pinfunction "1_1") (pintype "passive"))
      (node (ref "D2") (pin "1") (pinfunction "A_1") (pintype "passive"))
      (node (ref "D3") (pin "1") (pinfunction "A_1") (pintype "passive"))
      (node (ref "J2") (pin "7") (pinfunction "7_7") (pintype "passive"))
      (node (ref "J3") (pin "1") (pinfunction "1_1") (pintype "passive"))
      (node (ref "J3") (pin "12") (pinfunction "12_12") (pintype "passive"))
      (node (ref "J3") (pin "16") (pinfunction "16_16") (pintype "passive"))
      (node (ref "J3") (pin "2") (pinfunction "2_2") (pintype "passive"))
      (node (ref "J3") (pin "3") (pinfunction "3_3") (pintype "passive"))
      (node (ref "J3") (pin "4") (pinfunction "4_4") (pintype "passive"))
      (node (ref "J5") (pin "2") (pinfunction "2_2") (pintype "passive"))
      (node (ref "J5") (pin "4") (pinfunction "4_4") (pintype "passive"))
      (node (ref "R1") (pin "2") (pinfunction "2_2") (pintype "passive"))
      (node (ref "R14") (pin "2") (pinfunction "2_2") (pintype "passive"))
      (node (ref "R2") (pin "1") (pinfunction "1_1") (pintype "passive"))
      (node (ref "R24") (pin "2") (pinfunction "2_2") (pintype "passive"))
      (node (ref "R3") (pin "1") (pinfunction "1_1") (pintype "passive"))
      (node (ref "R7") (pin "1") (pinfunction "1_1") (pintype "passive"))
      (node (ref "S3") (pin "3") (pinfunction "3_3") (pintype "passive"))
      (node (ref "U3") (pin "14") (pinfunction "VDD33/VIO_14") (pintype "power_in"))
    )
    (net (code "84") (name "5V_in") (class "Default")
      (node (ref "F2") (pin "1") (pinfunction "1_1") (pintype "passive"))
      (node (ref "P6") (pin "A4") (pinfunction "VBUS_A4") (pintype "bidirectional"))
      (node (ref "P6") (pin "B4") (pinfunction "VBUS_B4") (pintype "bidirectional"))
      (node (ref "P7") (pin "A4") (pinfunction "VBUS_A4") (pintype "bidirectional"))
      (node (ref "P7") (pin "B4") (pinfunction "VBUS_B4") (pintype "bidirectional"))
      (node (ref "P9") (pin "A4") (pinfunction "VBUS_A4") (pintype "bidirectional"))
      (node (ref "P9") (pin "B4") (pinfunction "VBUS_B4") (pintype "bidirectional"))
    )
    (net (code "85") (name "GND") (class "Default")
      (node (ref "C1") (pin "1") (pinfunction "1_1") (pintype "passive"))
      (node (ref "C10") (pin "2") (pinfunction "2_2") (pintype "passive"))
      (node (ref "C11") (pin "1") (pinfunction "1_1") (pintype "passive"))
      (node (ref "C12") (pin "2") (pinfunction "2_2") (pintype "passive"))
      (node (ref "C13") (pin "2") (pinfunction "2_2") (pintype "passive"))
      (node (ref "C2") (pin "1") (pinfunction "1_1") (pintype "passive"))
      (node (ref "C21") (pin "2") (pinfunction "2_2") (pintype "passive"))
      (node (ref "C3") (pin "1") (pinfunction "1_1") (pintype "passive"))
      (node (ref "C31") (pin "1") (pinfunction "1_1") (pintype "passive"))
      (node (ref "C32") (pin "1") (pinfunction "1_1") (pintype "passive"))
      (node (ref "C4") (pin "1") (pinfunction "1_1") (pintype "passive"))
      (node (ref "C5") (pin "2") (pinfunction "2_2") (pintype "passive"))
      (node (ref "C6") (pin "2") (pinfunction "2_2") (pintype "passive"))
      (node (ref "C7") (pin "1") (pinfunction "1_1") (pintype "passive"))
      (node (ref "C8") (pin "1") (pinfunction "1_1") (pintype "passive"))
      (node (ref "C9") (pin "2") (pinfunction "2_2") (pintype "passive"))
      (node (ref "J2") (pin "5") (pinfunction "5_5") (pintype "passive"))
      (node (ref "J2") (pin "6") (pinfunction "6_6") (pintype "passive"))
      (node (ref "J3") (pin "19") (pinfunction "19_19") (pintype "passive"))
      (node (ref "J3") (pin "20") (pinfunction "20_20") (pintype "passive"))
      (node (ref "J3") (pin "21") (pinfunction "21_21") (pintype "passive"))
      (node (ref "J3") (pin "22") (pinfunction "22_22") (pintype "passive"))
      (node (ref "J3") (pin "7") (pinfunction "7_7") (pintype "passive"))
      (node (ref "J3") (pin "8") (pinfunction "8_8") (pintype "passive"))
      (node (ref "J4") (pin "32") (pinfunction "32_32") (pintype "passive"))
      (node (ref "J4") (pin "7") (pinfunction "7_7") (pintype "passive"))
      (node (ref "J5") (pin "6") (pinfunction "6_6") (pintype "passive"))
      (node (ref "J5") (pin "7") (pinfunction "7_7") (pintype "passive"))
      (node (ref "J7") (pin "4") (pinfunction "4_4") (pintype "passive"))
      (node (ref "P6") (pin "A1") (pinfunction "GND_A1") (pintype "bidirectional"))
      (node (ref "P6") (pin "B1") (pinfunction "GND_B1") (pintype "bidirectional"))
      (node (ref "P7") (pin "A1") (pinfunction "GND_A1") (pintype "bidirectional"))
      (node (ref "P7") (pin "B1") (pinfunction "GND_B1") (pintype "bidirectional"))
      (node (ref "P9") (pin "A1") (pinfunction "GND_A1") (pintype "bidirectional"))
      (node (ref "P9") (pin "B1") (pinfunction "GND_B1") (pintype "bidirectional"))
      (node (ref "PWR") (pin "2") (pinfunction "K_2") (pintype "passive"))
      (node (ref "R10") (pin "2") (pinfunction "2_2") (pintype "passive"))
      (node (ref "R11") (pin "2") (pinfunction "2_2") (pintype "passive"))
      (node (ref "R18") (pin "1") (pinfunction "1_1") (pintype "passive"))
      (node (ref "R21") (pin "1") (pinfunction "1_1") (pintype "passive"))
      (node (ref "R22") (pin "1") (pinfunction "1_1") (pintype "passive"))
      (node (ref "R25") (pin "1") (pinfunction "1_1") (pintype "passive"))
      (node (ref "R8") (pin "1") (pinfunction "1_1") (pintype "passive"))
      (node (ref "R9") (pin "1") (pinfunction "1_1") (pintype "passive"))
      (node (ref "S1") (pin "3") (pinfunction "B1_3") (pintype "passive"))
      (node (ref "S2") (pin "3") (pinfunction "B1_3") (pintype "passive"))
      (node (ref "S5") (pin "2") (pinfunction "2_2") (pintype "passive"))
      (node (ref "U1") (pin "1") (pinfunction "GND_1") (pintype "passive"))
      (node (ref "U2") (pin "12") (pinfunction "VSSA_12") (pintype "power_in"))
      (node (ref "U2") (pin "18") (pinfunction "VSS_4_18") (pintype "power_in"))
      (node (ref "U2") (pin "31") (pinfunction "VSS_1_31") (pintype "power_in"))
      (node (ref "U2") (pin "63") (pinfunction "VSS_3_63") (pintype "power_in"))
      (node (ref "U3") (pin "18") (pinfunction "VSS/GND_18") (pintype "power_in"))
    )
    (net (code "86") (name "Net-(D2-K)") (class "Default")
      (node (ref "D2") (pin "2") (pinfunction "K_2") (pintype "passive"))
      (node (ref "R13") (pin "2") (pinfunction "2_2") (pintype "passive"))
    )
    (net (code "87") (name "Net-(D3-K)") (class "Default")
      (node (ref "D3") (pin "2") (pinfunction "K_2") (pintype "passive"))
      (node (ref "R21") (pin "2") (pinfunction "2_2") (pintype "passive"))
    )
    (net (code "88") (name "Net-(J3-Pad6)") (class "Default")
      (node (ref "J3") (pin "6") (pinfunction "6_6") (pintype "passive"))
      (node (ref "R5") (pin "1") (pinfunction "1_1") (pintype "passive"))
    )
    (net (code "89") (name "Net-(J3-Pad10)") (class "Default")
      (node (ref "J3") (pin "10") (pinfunction "10_10") (pintype "passive"))
      (node (ref "J5") (pin "1") (pinfunction "1_1") (pintype "passive"))
    )
    (net (code "90") (name "Net-(LED1-A)") (class "Default")
      (node (ref "LED1") (pin "1") (pinfunction "A_1") (pintype "passive"))
      (node (ref "R2") (pin "2") (pinfunction "2_2") (pintype "passive"))
    )
    (net (code "91") (name "Net-(LED2-A)") (class "Default")
      (node (ref "LED2") (pin "1") (pinfunction "A_1") (pintype "passive"))
      (node (ref "R3") (pin "2") (pinfunction "2_2") (pintype "passive"))
    )
    (net (code "92") (name "Net-(P6-CC-PadA5)") (class "Default")
      (node (ref "P6") (pin "A5") (pinfunction "CC_A5") (pintype "bidirectional"))
      (node (ref "R18") (pin "2") (pinfunction "2_2") (pintype "passive"))
    )
    (net (code "93") (name "Net-(P6-CC-PadB5)") (class "Default")
      (node (ref "P6") (pin "B5") (pinfunction "CC_B5") (pintype "bidirectional"))
      (node (ref "R25") (pin "2") (pinfunction "2_2") (pintype "passive"))
    )
    (net (code "94") (name "Net-(P7-CC-PadA5)") (class "Default")
      (node (ref "P7") (pin "A5") (pinfunction "CC_A5") (pintype "bidirectional"))
      (node (ref "R8") (pin "2") (pinfunction "2_2") (pintype "passive"))
    )
    (net (code "95") (name "Net-(P7-CC-PadB5)") (class "Default")
      (node (ref "P7") (pin "B5") (pinfunction "CC_B5") (pintype "bidirectional"))
      (node (ref "R9") (pin "2") (pinfunction "2_2") (pintype "passive"))
    )
    (net (code "96") (name "Net-(P9-CC-PadA5)") (class "Default")
      (node (ref "P9") (pin "A5") (pinfunction "CC_A5") (pintype "bidirectional"))
      (node (ref "R10") (pin "1") (pinfunction "1_1") (pintype "passive"))
    )
    (net (code "97") (name "Net-(P9-CC-PadB5)") (class "Default")
      (node (ref "P9") (pin "B5") (pinfunction "CC_B5") (pintype "bidirectional"))
      (node (ref "R11") (pin "1") (pinfunction "1_1") (pintype "passive"))
    )
    (net (code "98") (name "Net-(PWR-A)") (class "Default")
      (node (ref "PWR") (pin "1") (pinfunction "A_1") (pintype "passive"))
      (node (ref "R1") (pin "1") (pinfunction "1_1") (pintype "passive"))
    )
    (net (code "99") (name "Net-(U1-VOUT)") (class "Default")
      (node (ref "C13") (pin "1") (pinfunction "1_1") (pintype "passive"))
      (node (ref "S3") (pin "1") (pinfunction "1_1") (pintype "passive"))
      (node (ref "U1") (pin "2") (pinfunction "VOUT_2") (pintype "passive"))
    )
    (net (code "100") (name "Net-(U2-VDD_2)") (class "Default")
      (node (ref "R16") (pin "2") (pinfunction "2_2") (pintype "passive"))
      (node (ref "U2") (pin "48") (pinfunction "VDD_2_48") (pintype "power_in"))
    )
    (net (code "101") (name "Net-(U2-VSS_2)") (class "Default")
      (node (ref "R22") (pin "2") (pinfunction "2_2") (pintype "passive"))
      (node (ref "U2") (pin "47") (pinfunction "VSS_2_47") (pintype "power_in"))
    )
    (net (code "102") (name "unconnected-(P6-RFU1-PadA8)") (class "Default")
      (node (ref "P6") (pin "A8") (pinfunction "RFU1_A8") (pintype "bidirectional+no_connect"))
    )
    (net (code "103") (name "unconnected-(P6-RFU1-PadB8)") (class "Default")
      (node (ref "P6") (pin "B8") (pinfunction "RFU1_B8") (pintype "bidirectional+no_connect"))
    )
    (net (code "104") (name "unconnected-(P7-RFU1-PadA8)") (class "Default")
      (node (ref "P7") (pin "A8") (pinfunction "RFU1_A8") (pintype "bidirectional+no_connect"))
    )
    (net (code "105") (name "unconnected-(P7-RFU1-PadB8)") (class "Default")
      (node (ref "P7") (pin "B8") (pinfunction "RFU1_B8") (pintype "bidirectional+no_connect"))
    )
    (net (code "106") (name "unconnected-(P9-RFU1-PadA8)") (class "Default")
      (node (ref "P9") (pin "A8") (pinfunction "RFU1_A8") (pintype "bidirectional+no_connect"))
    )
    (net (code "107") (name "unconnected-(P9-RFU1-PadB8)") (class "Default")
      (node (ref "P9") (pin "B8") (pinfunction "RFU1_B8") (pintype "bidirectional+no_connect"))
    )
    (net (code "108") (name "unconnected-(S1-A1-Pad4)") (class "Default")
      (node (ref "S1") (pin "4") (pinfunction "A1_4") (pintype "passive"))
    )
    (net (code "109") (name "unconnected-(S1-B0-Pad2)") (class "Default")
      (node (ref "S1") (pin "2") (pinfunction "B0_2") (pintype "passive"))
    )
    (net (code "110") (name "unconnected-(S2-A1-Pad4)") (class "Default")
      (node (ref "S2") (pin "4") (pinfunction "A1_4") (pintype "passive"))
    )
    (net (code "111") (name "unconnected-(S2-B0-Pad2)") (class "Default")
      (node (ref "S2") (pin "2") (pinfunction "B0_2") (pintype "passive"))
    )
    (net (code "112") (name "unconnected-(S3-Pad2)") (class "Default")
      (node (ref "S3") (pin "2") (pinfunction "2_2") (pintype "passive"))
    )
    (net (code "113") (name "unconnected-(U3-PA5{slash}UART1_CTS{slash}PA1_(no5V)-Pad2)") (class "Default")
      (node (ref "U3") (pin "2") (pinfunction "PA5/UART1_CTS/PA1_(no5V)_2") (pintype "bidirectional+no_connect"))
    )
    (net (code "114") (name "unconnected-(U3-PB12{slash}SPI2_NSS{slash}CAN2_RX-Pad5)") (class "Default")
      (node (ref "U3") (pin "5") (pinfunction "PB12/SPI2_NSS/CAN2_RX_5") (pintype "bidirectional+no_connect"))
    )
    (net (code "115") (name "unconnected-(U3-PB14{slash}SPI2_MISO{slash}UART3_RTS-Pad7)") (class "Default")
      (node (ref "U3") (pin "7") (pinfunction "PB14/SPI2_MISO/UART3_RTS_7") (pintype "bidirectional+no_connect"))
    )
    (net (code "116") (name "unconnected-(U3-PB15{slash}SPI2_MOSI{slash}UART1_TX-Pad8)") (class "Default")
      (node (ref "U3") (pin "8") (pinfunction "PB15/SPI2_MOSI/UART1_TX_8") (pintype "bidirectional+no_connect"))
    )
  )
)
